# Noise-box-v001.net
KiCad netlist of a schematic drawn in EAGLE
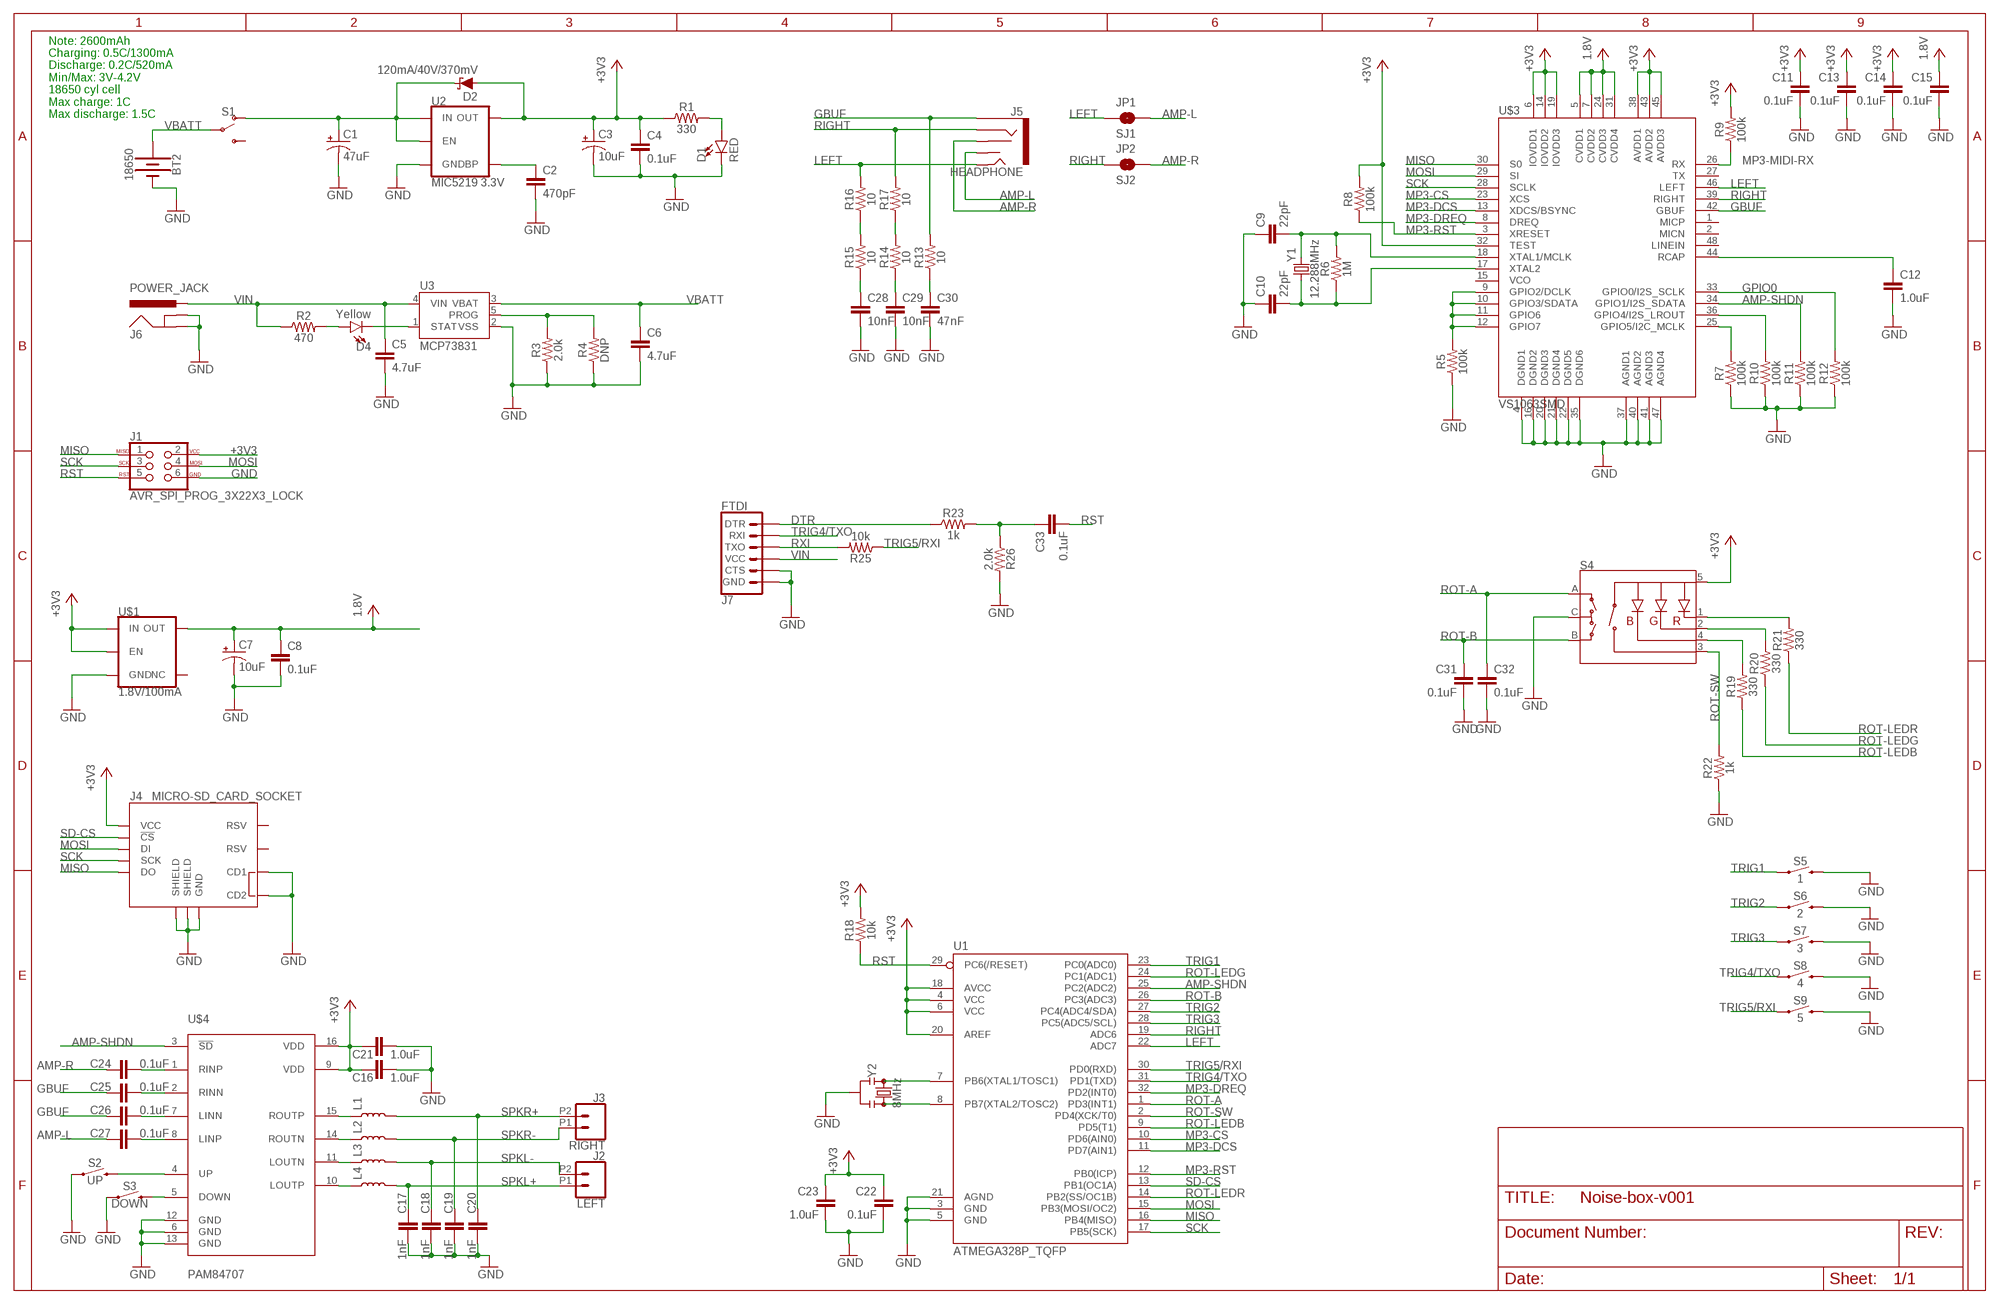
[diagram p0: schematic, sheet 1]

(export (version "E")
  (design (tool "Eeschema 10.0.6"))
  (components
    (comp (ref "BT2")
      (value "18650")
      (footprint "eagle-import:BATTERY_18650-1043P")
      (fields (field (name "MANUFACTURER") "keystone electronics") (field (name "PARTNO") "1043p"))
      (libsource (lib "eagle-import") (part "BATTERY-1043P"))
    )
    (comp (ref "C1")
      (value "47uF")
      (footprint "eagle-import:EIA3528")
      (libsource (lib "eagle-import") (part "47UF-POLAR-EIA3528-10V-10%"))
    )
    (comp (ref "C2")
      (value "470pF")
      (footprint "eagle-import:0603")
      (libsource (lib "eagle-import") (part "470PF-0603-50V-5%"))
    )
    (comp (ref "C3")
      (value "10uF")
      (footprint "eagle-import:EIA3216")
      (libsource (lib "eagle-import") (part "10UF-POLAR-EIA3216-16V-10%(TANT)"))
    )
    (comp (ref "C4")
      (value "0.1uF")
      (footprint "eagle-import:0603")
      (libsource (lib "eagle-import") (part "0.1UF-0603-25V-5%"))
    )
    (comp (ref "C5")
      (value "4.7uF")
      (footprint "eagle-import:0603")
      (libsource (lib "eagle-import") (part "4.7UF0603"))
    )
    (comp (ref "C6")
      (value "4.7uF")
      (footprint "eagle-import:0603")
      (libsource (lib "eagle-import") (part "4.7UF0603"))
    )
    (comp (ref "C7")
      (value "10uF")
      (footprint "eagle-import:EIA3216")
      (libsource (lib "eagle-import") (part "10UF-POLAR-EIA3216-16V-10%(TANT)"))
    )
    (comp (ref "C8")
      (value "0.1uF")
      (footprint "eagle-import:0603")
      (libsource (lib "eagle-import") (part "0.1UF-0603-25V-5%"))
    )
    (comp (ref "C9")
      (value "22pF")
      (footprint "eagle-import:0603")
      (libsource (lib "eagle-import") (part "22PF-0603-50V-5%"))
    )
    (comp (ref "C10")
      (value "22pF")
      (footprint "eagle-import:0603")
      (libsource (lib "eagle-import") (part "22PF-0603-50V-5%"))
    )
    (comp (ref "C11")
      (value "0.1uF")
      (footprint "eagle-import:0603")
      (libsource (lib "eagle-import") (part "0.1UF-0603-25V-5%"))
    )
    (comp (ref "C12")
      (value "1.0uF")
      (footprint "eagle-import:0603")
      (libsource (lib "eagle-import") (part "1.0UF-0603-16V-10%"))
    )
    (comp (ref "C13")
      (value "0.1uF")
      (footprint "eagle-import:0603")
      (libsource (lib "eagle-import") (part "0.1UF-0603-25V-5%"))
    )
    (comp (ref "C14")
      (value "0.1uF")
      (footprint "eagle-import:0603")
      (libsource (lib "eagle-import") (part "0.1UF-0603-25V-5%"))
    )
    (comp (ref "C15")
      (value "0.1uF")
      (footprint "eagle-import:0603")
      (libsource (lib "eagle-import") (part "0.1UF-0603-25V-5%"))
    )
    (comp (ref "C16")
      (value "1.0uF")
      (footprint "eagle-import:0603")
      (libsource (lib "eagle-import") (part "1.0UF-0603-16V-10%"))
    )
    (comp (ref "C17")
      (value "1nF")
      (footprint "eagle-import:0603")
      (libsource (lib "eagle-import") (part "1.0NF/1000PF-0603-50V-10%"))
    )
    (comp (ref "C18")
      (value "1nF")
      (footprint "eagle-import:0603")
      (libsource (lib "eagle-import") (part "1.0NF/1000PF-0603-50V-10%"))
    )
    (comp (ref "C19")
      (value "1nF")
      (footprint "eagle-import:0603")
      (libsource (lib "eagle-import") (part "1.0NF/1000PF-0603-50V-10%"))
    )
    (comp (ref "C20")
      (value "1nF")
      (footprint "eagle-import:0603")
      (libsource (lib "eagle-import") (part "1.0NF/1000PF-0603-50V-10%"))
    )
    (comp (ref "C21")
      (value "1.0uF")
      (footprint "eagle-import:0603")
      (libsource (lib "eagle-import") (part "1.0UF-0603-16V-10%"))
    )
    (comp (ref "C22")
      (value "0.1uF")
      (footprint "eagle-import:0603")
      (libsource (lib "eagle-import") (part "0.1UF-0603-25V-5%"))
    )
    (comp (ref "C23")
      (value "1.0uF")
      (footprint "eagle-import:0603")
      (libsource (lib "eagle-import") (part "1.0UF-0603-16V-10%"))
    )
    (comp (ref "C24")
      (value "0.1uF")
      (footprint "eagle-import:0603")
      (libsource (lib "eagle-import") (part "0.1UF-0603-25V-5%"))
    )
    (comp (ref "C25")
      (value "0.1uF")
      (footprint "eagle-import:0603")
      (libsource (lib "eagle-import") (part "0.1UF-0603-25V-5%"))
    )
    (comp (ref "C26")
      (value "0.1uF")
      (footprint "eagle-import:0603")
      (libsource (lib "eagle-import") (part "0.1UF-0603-25V-5%"))
    )
    (comp (ref "C27")
      (value "0.1uF")
      (footprint "eagle-import:0603")
      (libsource (lib "eagle-import") (part "0.1UF-0603-25V-5%"))
    )
    (comp (ref "C28")
      (value "10nF")
      (footprint "eagle-import:0603")
      (libsource (lib "eagle-import") (part "10NF-0603-50V-10%"))
    )
    (comp (ref "C29")
      (value "10nF")
      (footprint "eagle-import:0603")
      (libsource (lib "eagle-import") (part "10NF-0603-50V-10%"))
    )
    (comp (ref "C30")
      (value "47nF")
      (footprint "eagle-import:0603")
      (libsource (lib "eagle-import") (part "47NF-0603-25V-5%"))
    )
    (comp (ref "C31")
      (value "0.1uF")
      (footprint "eagle-import:0603")
      (libsource (lib "eagle-import") (part "0.1UF-0603-25V-5%"))
    )
    (comp (ref "C32")
      (value "0.1uF")
      (footprint "eagle-import:0603")
      (libsource (lib "eagle-import") (part "0.1UF-0603-25V-5%"))
    )
    (comp (ref "C33")
      (value "0.1uF")
      (footprint "eagle-import:0603")
      (libsource (lib "eagle-import") (part "0.1UF-0603-25V-5%"))
    )
    (comp (ref "D1")
      (value "RED")
      (footprint "eagle-import:LED-0603")
      (libsource (lib "eagle-import") (part "LED-RED0603"))
    )
    (comp (ref "D2")
      (value "120mA/40V/370mV")
      (footprint "eagle-import:SOD-523")
      (libsource (lib "eagle-import") (part "DIODE-SCHOTTKY-RB751S40"))
    )
    (comp (ref "D4")
      (value "Yellow")
      (footprint "eagle-import:LED-0603")
      (libsource (lib "eagle-import") (part "LED-YELLOW0603"))
    )
    (comp (ref "J1")
      (value "AVR_SPI_PROG_3X22X3_LOCK")
      (footprint "eagle-import:2X3_LOCK")
      (libsource (lib "eagle-import") (part "AVR_SPI_PROG_3X22X3_LOCK"))
    )
    (comp (ref "J2")
      (value "LEFT")
      (footprint "eagle-import:1X02_2.54_SCREWTERM")
      (libsource (lib "eagle-import") (part "CONN_022.54MM_SCREWTERM"))
    )
    (comp (ref "J3")
      (value "RIGHT")
      (footprint "eagle-import:1X02_2.54_SCREWTERM")
      (libsource (lib "eagle-import") (part "CONN_022.54MM_SCREWTERM"))
    )
    (comp (ref "J4")
      (value "MICRO-SD_CARD_SOCKET")
      (footprint "eagle-import:MICRO-SD-SOCKET")
      (libsource (lib "eagle-import") (part "MICRO-SD_CARD_SOCKET"))
    )
    (comp (ref "J5")
      (value "HEADPHONE")
      (footprint "eagle-import:AUDIO-JACK-3.5MM-SMD")
      (libsource (lib "eagle-import") (part "AUDIO_JACK_3.5MM_SMD"))
    )
    (comp (ref "J6")
      (value "POWER_JACK")
      (footprint "eagle-import:POWER_JACK_PTH")
      (libsource (lib "eagle-import") (part "POWER_JACK"))
    )
    (comp (ref "J7")
      (value "FTDI")
      (footprint "eagle-import:6_PIN_SERIAL_TARGET_SIDE_W_SILK")
      (libsource (lib "eagle-import") (part "6_PIN_SERIAL_TARGETSILK"))
    )
    (comp (ref "JP1")
      (value "SJ1")
      (footprint "eagle-import:SMT-JUMPER_2_NO_SILK")
      (libsource (lib "eagle-import") (part "JUMPER-SMT_2_NO_SILK"))
    )
    (comp (ref "JP2")
      (value "SJ2")
      (footprint "eagle-import:SMT-JUMPER_2_NO_SILK")
      (libsource (lib "eagle-import") (part "JUMPER-SMT_2_NO_SILK"))
    )
    (comp (ref "L1")
      (value "INDUCTOR-0805-3.3UH")
      (footprint "eagle-import:0805")
      (libsource (lib "eagle-import") (part "INDUCTOR-0805-3.3UH"))
    )
    (comp (ref "L2")
      (value "INDUCTOR-0805-3.3UH")
      (footprint "eagle-import:0805")
      (libsource (lib "eagle-import") (part "INDUCTOR-0805-3.3UH"))
    )
    (comp (ref "L3")
      (value "INDUCTOR-0805-3.3UH")
      (footprint "eagle-import:0805")
      (libsource (lib "eagle-import") (part "INDUCTOR-0805-3.3UH"))
    )
    (comp (ref "L4")
      (value "INDUCTOR-0805-3.3UH")
      (footprint "eagle-import:0805")
      (libsource (lib "eagle-import") (part "INDUCTOR-0805-3.3UH"))
    )
    (comp (ref "R1")
      (value "330")
      (footprint "eagle-import:0603")
      (libsource (lib "eagle-import") (part "330OHM-0603-1/10W-1%"))
    )
    (comp (ref "R2")
      (value "470")
      (footprint "eagle-import:0603")
      (libsource (lib "eagle-import") (part "470OHM-0603-1/10W-1%"))
    )
    (comp (ref "R3")
      (value "2.0k")
      (footprint "eagle-import:0603")
      (libsource (lib "eagle-import") (part "2.0KOHM-0603-1/10W-5%"))
    )
    (comp (ref "R4")
      (value "DNP")
      (footprint "eagle-import:0603")
      (libsource (lib "eagle-import") (part "2.0KOHM-0603-1/10W-5%"))
    )
    (comp (ref "R5")
      (value "100k")
      (footprint "eagle-import:0603")
      (libsource (lib "eagle-import") (part "100KOHM-0603-1/10W-1%"))
    )
    (comp (ref "R6")
      (value "1M")
      (footprint "eagle-import:0603")
      (libsource (lib "eagle-import") (part "1MOHM-0603-1/4W-5%"))
    )
    (comp (ref "R7")
      (value "100k")
      (footprint "eagle-import:0603")
      (libsource (lib "eagle-import") (part "100KOHM-0603-1/10W-1%"))
    )
    (comp (ref "R8")
      (value "100k")
      (footprint "eagle-import:0603")
      (libsource (lib "eagle-import") (part "100KOHM-0603-1/10W-1%"))
    )
    (comp (ref "R9")
      (value "100k")
      (footprint "eagle-import:0603")
      (libsource (lib "eagle-import") (part "100KOHM-0603-1/10W-1%"))
    )
    (comp (ref "R10")
      (value "100k")
      (footprint "eagle-import:0603")
      (libsource (lib "eagle-import") (part "100KOHM-0603-1/10W-1%"))
    )
    (comp (ref "R11")
      (value "100k")
      (footprint "eagle-import:0603")
      (libsource (lib "eagle-import") (part "100KOHM-0603-1/10W-1%"))
    )
    (comp (ref "R12")
      (value "100k")
      (footprint "eagle-import:0603")
      (libsource (lib "eagle-import") (part "100KOHM-0603-1/10W-1%"))
    )
    (comp (ref "R13")
      (value "10")
      (footprint "eagle-import:0603")
      (libsource (lib "eagle-import") (part "10OHM-0603-1/10W-5%"))
    )
    (comp (ref "R14")
      (value "10")
      (footprint "eagle-import:0603")
      (libsource (lib "eagle-import") (part "10OHM-0603-1/10W-5%"))
    )
    (comp (ref "R15")
      (value "10")
      (footprint "eagle-import:0603")
      (libsource (lib "eagle-import") (part "10OHM-0603-1/10W-5%"))
    )
    (comp (ref "R16")
      (value "10")
      (footprint "eagle-import:0603")
      (libsource (lib "eagle-import") (part "10OHM-0603-1/10W-5%"))
    )
    (comp (ref "R17")
      (value "10")
      (footprint "eagle-import:0603")
      (libsource (lib "eagle-import") (part "10OHM-0603-1/10W-5%"))
    )
    (comp (ref "R18")
      (value "10k")
      (footprint "eagle-import:0603")
      (libsource (lib "eagle-import") (part "10KOHM-0603-1/10W-1%"))
    )
    (comp (ref "R19")
      (value "330")
      (footprint "eagle-import:0603")
      (libsource (lib "eagle-import") (part "330OHM-0603-1/10W-1%"))
    )
    (comp (ref "R20")
      (value "330")
      (footprint "eagle-import:0603")
      (libsource (lib "eagle-import") (part "330OHM-0603-1/10W-1%"))
    )
    (comp (ref "R21")
      (value "330")
      (footprint "eagle-import:0603")
      (libsource (lib "eagle-import") (part "330OHM-0603-1/10W-1%"))
    )
    (comp (ref "R22")
      (value "1k")
      (footprint "eagle-import:0603")
      (libsource (lib "eagle-import") (part "1KOHM-0603-1/10W-1%"))
    )
    (comp (ref "R23")
      (value "1k")
      (footprint "eagle-import:0603")
      (libsource (lib "eagle-import") (part "1KOHM-0603-1/10W-1%"))
    )
    (comp (ref "R25")
      (value "10k")
      (footprint "eagle-import:0603")
      (libsource (lib "eagle-import") (part "10KOHM-0603-1/10W-1%"))
    )
    (comp (ref "R26")
      (value "2.0k")
      (footprint "eagle-import:0603")
      (libsource (lib "eagle-import") (part "2.0KOHM-0603-1/10W-5%"))
    )
    (comp (ref "S1")
      (value "SWITCH-SPDT-SMD-RIGHT-ANGLE")
      (footprint "eagle-import:SWITCH_SPST_SMD_A")
      (libsource (lib "eagle-import") (part "SWITCH-SPDT-SMD-RIGHT-ANGLE"))
    )
    (comp (ref "S2")
      (value "UP")
      (footprint "eagle-import:TACTILE_SWITCH_SMD_4.5MM")
      (libsource (lib "eagle-import") (part "MOMENTARY-SWITCH-SPST-SMD-4.5MM"))
    )
    (comp (ref "S3")
      (value "DOWN")
      (footprint "eagle-import:TACTILE_SWITCH_SMD_4.5MM")
      (libsource (lib "eagle-import") (part "MOMENTARY-SWITCH-SPST-SMD-4.5MM"))
    )
    (comp (ref "S4")
      (value "ENCODER-RGB-SWITCH")
      (footprint "eagle-import:ENCODER_LED_3")
      (libsource (lib "eagle-import") (part "ENCODER-RGB-SWITCH"))
    )
    (comp (ref "S5")
      (value "1")
      (footprint "eagle-import:TACTILE_SWITCH_SMD_4.5MM")
      (libsource (lib "eagle-import") (part "MOMENTARY-SWITCH-SPST-SMD-4.5MM"))
    )
    (comp (ref "S6")
      (value "2")
      (footprint "eagle-import:TACTILE_SWITCH_SMD_4.5MM")
      (libsource (lib "eagle-import") (part "MOMENTARY-SWITCH-SPST-SMD-4.5MM"))
    )
    (comp (ref "S7")
      (value "3")
      (footprint "eagle-import:TACTILE_SWITCH_SMD_4.5MM")
      (libsource (lib "eagle-import") (part "MOMENTARY-SWITCH-SPST-SMD-4.5MM"))
    )
    (comp (ref "S8")
      (value "4")
      (footprint "eagle-import:TACTILE_SWITCH_SMD_4.5MM")
      (libsource (lib "eagle-import") (part "MOMENTARY-SWITCH-SPST-SMD-4.5MM"))
    )
    (comp (ref "S9")
      (value "5")
      (footprint "eagle-import:TACTILE_SWITCH_SMD_4.5MM")
      (libsource (lib "eagle-import") (part "MOMENTARY-SWITCH-SPST-SMD-4.5MM"))
    )
    (comp (ref "U$1")
      (value "1.8V/100mA")
      (footprint "eagle-import:SC70")
      (libsource (lib "eagle-import") (part "V_REG_SP6214-1.8V"))
    )
    (comp (ref "U$3")
      (value "VS1063SMD")
      (footprint "eagle-import:LQFP-48")
      (libsource (lib "eagle-import") (part "VS1063SMD"))
    )
    (comp (ref "U$4")
      (value "PAM84707")
      (footprint "eagle-import:SO16")
      (fields (field (name "PARTNO") "PAM8407DRDICT-ND"))
      (libsource (lib "eagle-import") (part "PAM8407"))
    )
    (comp (ref "U1")
      (value "ATMEGA328P_TQFP")
      (footprint "eagle-import:TQFP32-08")
      (libsource (lib "eagle-import") (part "ATMEGA328P_TQFP"))
    )
    (comp (ref "U2")
      (value "MIC5219 3.3V")
      (footprint "eagle-import:SOT23-5")
      (libsource (lib "eagle-import") (part "V_REG_MIC52193.3V"))
    )
    (comp (ref "U3")
      (value "MCP73831")
      (footprint "eagle-import:SOT23-5")
      (libsource (lib "eagle-import") (part "MCP73831"))
    )
    (comp (ref "Y1")
      (value "12.288MHz")
      (footprint "eagle-import:CRYSTAL-SMD-5X3.2-4PAD")
      (libsource (lib "eagle-import") (part "CRYSTAL-12.288MHZ{dblquote}"))
    )
    (comp (ref "Y2")
      (value "8MHz")
      (footprint "eagle-import:RESONATOR-SMD-3.2X1.3")
      (libsource (lib "eagle-import") (part "RESONATOR-8MHZSMD_3.2X1.3"))
    )
  )
  (nets
    (net (code "1") (name "+3V3") (class "Default")
      (node (ref "C11") (pin "1") (pinfunction "1_1") (pintype "passive"))
      (node (ref "C13") (pin "1") (pinfunction "1_1") (pintype "passive"))
      (node (ref "C14") (pin "1") (pinfunction "1_1") (pintype "passive"))
      (node (ref "C16") (pin "1") (pinfunction "1_1") (pintype "passive"))
      (node (ref "C21") (pin "1") (pinfunction "1_1") (pintype "passive"))
      (node (ref "C22") (pin "1") (pinfunction "1_1") (pintype "passive"))
      (node (ref "C23") (pin "1") (pinfunction "1_1") (pintype "passive"))
      (node (ref "C3") (pin "+") (pinfunction "+_+") (pintype "passive"))
      (node (ref "C4") (pin "1") (pinfunction "1_1") (pintype "passive"))
      (node (ref "D2") (pin "A") (pinfunction "A_A") (pintype "passive"))
      (node (ref "J1") (pin "2") (pinfunction "2_2") (pintype "passive"))
      (node (ref "J4") (pin "VCC") (pinfunction "VCC_VCC") (pintype "bidirectional"))
      (node (ref "R1") (pin "1") (pinfunction "1_1") (pintype "passive"))
      (node (ref "R18") (pin "2") (pinfunction "2_2") (pintype "passive"))
      (node (ref "R8") (pin "2") (pinfunction "2_2") (pintype "passive"))
      (node (ref "R9") (pin "2") (pinfunction "2_2") (pintype "passive"))
      (node (ref "S4") (pin "5") (pinfunction "+_5") (pintype "passive"))
      (node (ref "U$1") (pin "1") (pinfunction "IN_1") (pintype "input"))
      (node (ref "U$1") (pin "3") (pinfunction "EN_3") (pintype "input"))
      (node (ref "U$3") (pin "14") (pinfunction "IOVDD2_14") (pintype "bidirectional"))
      (node (ref "U$3") (pin "19") (pinfunction "IOVDD3_19") (pintype "bidirectional"))
      (node (ref "U$3") (pin "32") (pinfunction "TEST_32") (pintype "bidirectional"))
      (node (ref "U$3") (pin "38") (pinfunction "AVDD1_38") (pintype "bidirectional"))
      (node (ref "U$3") (pin "43") (pinfunction "AVDD2_43") (pintype "bidirectional"))
      (node (ref "U$3") (pin "45") (pinfunction "AVDD3_45") (pintype "bidirectional"))
      (node (ref "U$3") (pin "6") (pinfunction "IOVDD1_6") (pintype "bidirectional"))
      (node (ref "U$4") (pin "16") (pinfunction "VDD_16") (pintype "bidirectional"))
      (node (ref "U$4") (pin "9") (pinfunction "VDD_9") (pintype "bidirectional"))
      (node (ref "U1") (pin "18") (pinfunction "AVCC_18") (pintype "bidirectional"))
      (node (ref "U1") (pin "20") (pinfunction "AREF_20") (pintype "bidirectional"))
      (node (ref "U1") (pin "4") (pinfunction "VCC_4") (pintype "bidirectional"))
      (node (ref "U1") (pin "6") (pinfunction "VCC_6") (pintype "bidirectional"))
      (node (ref "U2") (pin "5") (pinfunction "OUT_5") (pintype "passive"))
    )
    (net (code "2") (name "/AMP-L") (class "Default")
      (node (ref "C27") (pin "1") (pinfunction "1_1") (pintype "passive"))
      (node (ref "J5") (pin "TSH") (pinfunction "TSH_TSH") (pintype "bidirectional"))
      (node (ref "JP1") (pin "2") (pinfunction "2_2") (pintype "passive"))
    )
    (net (code "3") (name "/AMP-R") (class "Default")
      (node (ref "C24") (pin "1") (pinfunction "1_1") (pintype "passive"))
      (node (ref "J5") (pin "RSH") (pinfunction "RSH_RSH") (pintype "bidirectional"))
      (node (ref "JP2") (pin "2") (pinfunction "2_2") (pintype "passive"))
    )
    (net (code "4") (name "/AMP-SHDN") (class "Default")
      (node (ref "R11") (pin "2") (pinfunction "2_2") (pintype "passive"))
      (node (ref "U$3") (pin "34") (pinfunction "GPIO1/I2S_SDATA_34") (pintype "bidirectional"))
      (node (ref "U$4") (pin "3") (pinfunction "~{SD}_3") (pintype "bidirectional"))
      (node (ref "U1") (pin "25") (pinfunction "PC2(ADC2)_25") (pintype "bidirectional"))
    )
    (net (code "5") (name "/DTR") (class "Default")
      (node (ref "J7") (pin "P$1") (pinfunction "DTR_P$1") (pintype "passive"))
      (node (ref "R23") (pin "1") (pinfunction "1_1") (pintype "passive"))
    )
    (net (code "6") (name "/GBUF") (class "Default")
      (node (ref "C25") (pin "1") (pinfunction "1_1") (pintype "passive"))
      (node (ref "C26") (pin "1") (pinfunction "1_1") (pintype "passive"))
      (node (ref "J5") (pin "SLEEVE") (pinfunction "SLEEVE_SLEEVE") (pintype "bidirectional"))
      (node (ref "R13") (pin "2") (pinfunction "2_2") (pintype "passive"))
      (node (ref "U$3") (pin "42") (pinfunction "GBUF_42") (pintype "bidirectional"))
    )
    (net (code "7") (name "/GPIO0") (class "Default")
      (node (ref "R12") (pin "2") (pinfunction "2_2") (pintype "passive"))
      (node (ref "U$3") (pin "33") (pinfunction "GPIO0/I2S_SCLK_33") (pintype "bidirectional"))
    )
    (net (code "8") (name "/LEFT") (class "Default")
      (node (ref "J5") (pin "TIP") (pinfunction "TIP_TIP") (pintype "bidirectional"))
      (node (ref "JP1") (pin "1") (pinfunction "1_1") (pintype "passive"))
      (node (ref "R16") (pin "2") (pinfunction "2_2") (pintype "passive"))
      (node (ref "U$3") (pin "46") (pinfunction "LEFT_46") (pintype "bidirectional"))
      (node (ref "U1") (pin "22") (pinfunction "ADC7_22") (pintype "bidirectional"))
    )
    (net (code "9") (name "/MISO") (class "Default")
      (node (ref "J1") (pin "1") (pinfunction "1_1") (pintype "passive"))
      (node (ref "J4") (pin "DO") (pinfunction "DO_DO") (pintype "bidirectional"))
      (node (ref "U$3") (pin "30") (pinfunction "S0_30") (pintype "bidirectional"))
      (node (ref "U1") (pin "16") (pinfunction "PB4(MISO)_16") (pintype "bidirectional"))
    )
    (net (code "10") (name "/MOSI") (class "Default")
      (node (ref "J1") (pin "4") (pinfunction "4_4") (pintype "passive"))
      (node (ref "J4") (pin "DI") (pinfunction "DI_DI") (pintype "bidirectional"))
      (node (ref "U$3") (pin "29") (pinfunction "SI_29") (pintype "bidirectional"))
      (node (ref "U1") (pin "15") (pinfunction "PB3(MOSI/OC2)_15") (pintype "bidirectional"))
    )
    (net (code "11") (name "/MP3-CS") (class "Default")
      (node (ref "U$3") (pin "23") (pinfunction "XCS_23") (pintype "bidirectional"))
      (node (ref "U1") (pin "10") (pinfunction "PD6(AIN0)_10") (pintype "bidirectional"))
    )
    (net (code "12") (name "/MP3-DCS") (class "Default")
      (node (ref "U$3") (pin "13") (pinfunction "XDCS/BSYNC_13") (pintype "bidirectional"))
      (node (ref "U1") (pin "11") (pinfunction "PD7(AIN1)_11") (pintype "bidirectional"))
    )
    (net (code "13") (name "/MP3-DREQ") (class "Default")
      (node (ref "U$3") (pin "8") (pinfunction "DREQ_8") (pintype "bidirectional"))
      (node (ref "U1") (pin "32") (pinfunction "PD2(INT0)_32") (pintype "bidirectional"))
    )
    (net (code "14") (name "/MP3-MIDI-RX") (class "Default")
      (node (ref "R9") (pin "1") (pinfunction "1_1") (pintype "passive"))
      (node (ref "U$3") (pin "26") (pinfunction "RX_26") (pintype "bidirectional"))
    )
    (net (code "15") (name "/MP3-RST") (class "Default")
      (node (ref "R8") (pin "1") (pinfunction "1_1") (pintype "passive"))
      (node (ref "U$3") (pin "3") (pinfunction "XRESET_3") (pintype "bidirectional"))
      (node (ref "U1") (pin "12") (pinfunction "PB0(ICP)_12") (pintype "bidirectional"))
    )
    (net (code "16") (name "/RIGHT") (class "Default")
      (node (ref "J5") (pin "RING") (pinfunction "RING_RING") (pintype "bidirectional"))
      (node (ref "JP2") (pin "1") (pinfunction "1_1") (pintype "passive"))
      (node (ref "R17") (pin "2") (pinfunction "2_2") (pintype "passive"))
      (node (ref "U$3") (pin "39") (pinfunction "RIGHT_39") (pintype "bidirectional"))
      (node (ref "U1") (pin "19") (pinfunction "ADC6_19") (pintype "bidirectional"))
    )
    (net (code "17") (name "/ROT-A") (class "Default")
      (node (ref "C32") (pin "1") (pinfunction "1_1") (pintype "passive"))
      (node (ref "S4") (pin "A") (pinfunction "A_A") (pintype "bidirectional"))
      (node (ref "U1") (pin "1") (pinfunction "PD3(INT1)_1") (pintype "bidirectional"))
    )
    (net (code "18") (name "/ROT-B") (class "Default")
      (node (ref "C31") (pin "1") (pinfunction "1_1") (pintype "passive"))
      (node (ref "S4") (pin "B") (pinfunction "B_B") (pintype "bidirectional"))
      (node (ref "U1") (pin "26") (pinfunction "PC3(ADC3)_26") (pintype "bidirectional"))
    )
    (net (code "19") (name "/ROT-LEDB") (class "Default")
      (node (ref "R19") (pin "1") (pinfunction "1_1") (pintype "passive"))
      (node (ref "U1") (pin "9") (pinfunction "PD5(T1)_9") (pintype "bidirectional"))
    )
    (net (code "20") (name "/ROT-LEDG") (class "Default")
      (node (ref "R20") (pin "1") (pinfunction "1_1") (pintype "passive"))
      (node (ref "U1") (pin "24") (pinfunction "PC1(ADC1)_24") (pintype "bidirectional"))
    )
    (net (code "21") (name "/ROT-LEDR") (class "Default")
      (node (ref "R21") (pin "1") (pinfunction "1_1") (pintype "passive"))
      (node (ref "U1") (pin "14") (pinfunction "PB2(SS/OC1B)_14") (pintype "bidirectional"))
    )
    (net (code "22") (name "/ROT-SW") (class "Default")
      (node (ref "R22") (pin "2") (pinfunction "2_2") (pintype "passive"))
      (node (ref "S4") (pin "3") (pinfunction "SW_3") (pintype "passive"))
      (node (ref "U1") (pin "2") (pinfunction "PD4(XCK/T0)_2") (pintype "bidirectional"))
    )
    (net (code "23") (name "/RST") (class "Default")
      (node (ref "C33") (pin "2") (pinfunction "2_2") (pintype "passive"))
      (node (ref "J1") (pin "5") (pinfunction "5_5") (pintype "passive"))
      (node (ref "R18") (pin "1") (pinfunction "1_1") (pintype "passive"))
      (node (ref "U1") (pin "29") (pinfunction "PC6(/RESET)_29") (pintype "bidirectional"))
    )
    (net (code "24") (name "/RXI") (class "Default")
      (node (ref "J7") (pin "P$2") (pinfunction "TXO_P$2") (pintype "passive"))
      (node (ref "R25") (pin "2") (pinfunction "2_2") (pintype "passive"))
    )
    (net (code "25") (name "/SCK") (class "Default")
      (node (ref "J1") (pin "3") (pinfunction "3_3") (pintype "passive"))
      (node (ref "J4") (pin "SCLK") (pinfunction "SCK_SCLK") (pintype "bidirectional"))
      (node (ref "U$3") (pin "28") (pinfunction "SCLK_28") (pintype "bidirectional"))
      (node (ref "U1") (pin "17") (pinfunction "PB5(SCK)_17") (pintype "bidirectional"))
    )
    (net (code "26") (name "/SD-CS") (class "Default")
      (node (ref "J4") (pin "CS") (pinfunction "~{CS}_CS") (pintype "bidirectional"))
      (node (ref "U1") (pin "13") (pinfunction "PB1(OC1A)_13") (pintype "bidirectional"))
    )
    (net (code "27") (name "/SPKL+") (class "Default")
      (node (ref "C17") (pin "1") (pinfunction "1_1") (pintype "passive"))
      (node (ref "J2") (pin "P1") (pinfunction "1_P1") (pintype "passive"))
      (node (ref "L4") (pin "2") (pinfunction "2_2") (pintype "passive"))
    )
    (net (code "28") (name "/SPKL-") (class "Default")
      (node (ref "C18") (pin "1") (pinfunction "1_1") (pintype "passive"))
      (node (ref "J2") (pin "P2") (pinfunction "2_P2") (pintype "passive"))
      (node (ref "L3") (pin "2") (pinfunction "2_2") (pintype "passive"))
    )
    (net (code "29") (name "/SPKR+") (class "Default")
      (node (ref "C20") (pin "1") (pinfunction "1_1") (pintype "passive"))
      (node (ref "J3") (pin "P2") (pinfunction "2_P2") (pintype "passive"))
      (node (ref "L1") (pin "2") (pinfunction "2_2") (pintype "passive"))
    )
    (net (code "30") (name "/SPKR-") (class "Default")
      (node (ref "C19") (pin "1") (pinfunction "1_1") (pintype "passive"))
      (node (ref "J3") (pin "P1") (pinfunction "1_P1") (pintype "passive"))
      (node (ref "L2") (pin "2") (pinfunction "2_2") (pintype "passive"))
    )
    (net (code "31") (name "/TRIG1") (class "Default")
      (node (ref "S5") (pin "2") (pinfunction "1_2") (pintype "passive"))
      (node (ref "S5") (pin "3") (pinfunction "1_3") (pintype "passive"))
      (node (ref "U1") (pin "23") (pinfunction "PC0(ADC0)_23") (pintype "bidirectional"))
    )
    (net (code "32") (name "/TRIG2") (class "Default")
      (node (ref "S6") (pin "2") (pinfunction "1_2") (pintype "passive"))
      (node (ref "S6") (pin "3") (pinfunction "1_3") (pintype "passive"))
      (node (ref "U1") (pin "27") (pinfunction "PC4(ADC4/SDA)_27") (pintype "bidirectional"))
    )
    (net (code "33") (name "/TRIG3") (class "Default")
      (node (ref "S7") (pin "2") (pinfunction "1_2") (pintype "passive"))
      (node (ref "S7") (pin "3") (pinfunction "1_3") (pintype "passive"))
      (node (ref "U1") (pin "28") (pinfunction "PC5(ADC5/SCL)_28") (pintype "bidirectional"))
    )
    (net (code "34") (name "/TRIG4{slash}TXO") (class "Default")
      (node (ref "J7") (pin "P$3") (pinfunction "RXI_P$3") (pintype "passive"))
      (node (ref "S8") (pin "2") (pinfunction "1_2") (pintype "passive"))
      (node (ref "S8") (pin "3") (pinfunction "1_3") (pintype "passive"))
      (node (ref "U1") (pin "31") (pinfunction "PD1(TXD)_31") (pintype "bidirectional"))
    )
    (net (code "35") (name "/TRIG5{slash}RXI") (class "Default")
      (node (ref "R25") (pin "1") (pinfunction "1_1") (pintype "passive"))
      (node (ref "S9") (pin "2") (pinfunction "1_2") (pintype "passive"))
      (node (ref "S9") (pin "3") (pinfunction "1_3") (pintype "passive"))
      (node (ref "U1") (pin "30") (pinfunction "PD0(RXD)_30") (pintype "bidirectional"))
    )
    (net (code "36") (name "/VBATT") (class "Default")
      (node (ref "BT2") (pin "PWR@1") (pinfunction "+_PWR@1") (pintype "power_in"))
      (node (ref "C6") (pin "1") (pinfunction "1_1") (pintype "passive"))
      (node (ref "S1") (pin "2") (pinfunction "P_2") (pintype "passive"))
      (node (ref "U3") (pin "3") (pinfunction "VBAT_3") (pintype "power_in"))
    )
    (net (code "37") (name "/VIN") (class "Default")
      (node (ref "C5") (pin "1") (pinfunction "1_1") (pintype "passive"))
      (node (ref "J6") (pin "PWR") (pinfunction "PWR_PWR") (pintype "bidirectional"))
      (node (ref "J7") (pin "P$4") (pinfunction "VCC_P$4") (pintype "passive"))
      (node (ref "R2") (pin "1") (pinfunction "1_1") (pintype "passive"))
      (node (ref "U3") (pin "4") (pinfunction "VIN_4") (pintype "power_in"))
    )
    (net (code "38") (name "1.8V") (class "Default")
      (node (ref "C15") (pin "1") (pinfunction "1_1") (pintype "passive"))
      (node (ref "C7") (pin "+") (pinfunction "+_+") (pintype "passive"))
      (node (ref "C8") (pin "1") (pinfunction "1_1") (pintype "passive"))
      (node (ref "U$1") (pin "5") (pinfunction "OUT_5") (pintype "passive"))
      (node (ref "U$3") (pin "24") (pinfunction "CVDD3_24") (pintype "bidirectional"))
      (node (ref "U$3") (pin "31") (pinfunction "CVDD4_31") (pintype "bidirectional"))
      (node (ref "U$3") (pin "5") (pinfunction "CVDD1_5") (pintype "bidirectional"))
      (node (ref "U$3") (pin "7") (pinfunction "CVDD2_7") (pintype "bidirectional"))
    )
    (net (code "39") (name "GND") (class "Default")
      (node (ref "BT2") (pin "GND@1") (pinfunction "-_GND@1") (pintype "power_in"))
      (node (ref "C1") (pin "C") (pinfunction "-_C") (pintype "passive"))
      (node (ref "C10") (pin "1") (pinfunction "1_1") (pintype "passive"))
      (node (ref "C11") (pin "2") (pinfunction "2_2") (pintype "passive"))
      (node (ref "C12") (pin "2") (pinfunction "2_2") (pintype "passive"))
      (node (ref "C13") (pin "2") (pinfunction "2_2") (pintype "passive"))
      (node (ref "C14") (pin "2") (pinfunction "2_2") (pintype "passive"))
      (node (ref "C15") (pin "2") (pinfunction "2_2") (pintype "passive"))
      (node (ref "C16") (pin "2") (pinfunction "2_2") (pintype "passive"))
      (node (ref "C17") (pin "2") (pinfunction "2_2") (pintype "passive"))
      (node (ref "C18") (pin "2") (pinfunction "2_2") (pintype "passive"))
      (node (ref "C19") (pin "2") (pinfunction "2_2") (pintype "passive"))
      (node (ref "C2") (pin "2") (pinfunction "2_2") (pintype "passive"))
      (node (ref "C20") (pin "2") (pinfunction "2_2") (pintype "passive"))
      (node (ref "C21") (pin "2") (pinfunction "2_2") (pintype "passive"))
      (node (ref "C22") (pin "2") (pinfunction "2_2") (pintype "passive"))
      (node (ref "C23") (pin "2") (pinfunction "2_2") (pintype "passive"))
      (node (ref "C28") (pin "2") (pinfunction "2_2") (pintype "passive"))
      (node (ref "C29") (pin "2") (pinfunction "2_2") (pintype "passive"))
      (node (ref "C3") (pin "-") (pinfunction "-_-") (pintype "passive"))
      (node (ref "C30") (pin "2") (pinfunction "2_2") (pintype "passive"))
      (node (ref "C31") (pin "2") (pinfunction "2_2") (pintype "passive"))
      (node (ref "C32") (pin "2") (pinfunction "2_2") (pintype "passive"))
      (node (ref "C4") (pin "2") (pinfunction "2_2") (pintype "passive"))
      (node (ref "C5") (pin "2") (pinfunction "2_2") (pintype "passive"))
      (node (ref "C6") (pin "2") (pinfunction "2_2") (pintype "passive"))
      (node (ref "C7") (pin "-") (pinfunction "-_-") (pintype "passive"))
      (node (ref "C8") (pin "2") (pinfunction "2_2") (pintype "passive"))
      (node (ref "C9") (pin "1") (pinfunction "1_1") (pintype "passive"))
      (node (ref "D1") (pin "C") (pinfunction "C_C") (pintype "passive"))
      (node (ref "J1") (pin "6") (pinfunction "6_6") (pintype "passive"))
      (node (ref "J4") (pin "CD1") (pinfunction "CD1_CD1") (pintype "bidirectional"))
      (node (ref "J4") (pin "CD2") (pinfunction "CD2_CD2") (pintype "bidirectional"))
      (node (ref "J4") (pin "GND") (pinfunction "GND_GND") (pintype "bidirectional"))
      (node (ref "J4") (pin "GND1") (pinfunction "SHIELD_GND1") (pintype "bidirectional"))
      (node (ref "J4") (pin "GND3") (pinfunction "SHIELD_GND3") (pintype "bidirectional"))
      (node (ref "J6") (pin "GND") (pinfunction "GND_GND") (pintype "bidirectional"))
      (node (ref "J6") (pin "GNDBREAK") (pinfunction "GNDBREAK_GNDBREAK") (pintype "bidirectional"))
      (node (ref "J7") (pin "P$5") (pinfunction "CTS_P$5") (pintype "passive"))
      (node (ref "J7") (pin "P$6") (pinfunction "GND_P$6") (pintype "passive"))
      (node (ref "R10") (pin "1") (pinfunction "1_1") (pintype "passive"))
      (node (ref "R11") (pin "1") (pinfunction "1_1") (pintype "passive"))
      (node (ref "R12") (pin "1") (pinfunction "1_1") (pintype "passive"))
      (node (ref "R22") (pin "1") (pinfunction "1_1") (pintype "passive"))
      (node (ref "R26") (pin "2") (pinfunction "2_2") (pintype "passive"))
      (node (ref "R3") (pin "1") (pinfunction "1_1") (pintype "passive"))
      (node (ref "R4") (pin "1") (pinfunction "1_1") (pintype "passive"))
      (node (ref "R5") (pin "1") (pinfunction "1_1") (pintype "passive"))
      (node (ref "R7") (pin "1") (pinfunction "1_1") (pintype "passive"))
      (node (ref "S2") (pin "2") (pinfunction "1_2") (pintype "passive"))
      (node (ref "S2") (pin "3") (pinfunction "1_3") (pintype "passive"))
      (node (ref "S3") (pin "2") (pinfunction "1_2") (pintype "passive"))
      (node (ref "S3") (pin "3") (pinfunction "1_3") (pintype "passive"))
      (node (ref "S4") (pin "C") (pinfunction "C_C") (pintype "bidirectional"))
      (node (ref "S5") (pin "1") (pinfunction "2_1") (pintype "passive"))
      (node (ref "S5") (pin "4") (pinfunction "2_4") (pintype "passive"))
      (node (ref "S6") (pin "1") (pinfunction "2_1") (pintype "passive"))
      (node (ref "S6") (pin "4") (pinfunction "2_4") (pintype "passive"))
      (node (ref "S7") (pin "1") (pinfunction "2_1") (pintype "passive"))
      (node (ref "S7") (pin "4") (pinfunction "2_4") (pintype "passive"))
      (node (ref "S8") (pin "1") (pinfunction "2_1") (pintype "passive"))
      (node (ref "S8") (pin "4") (pinfunction "2_4") (pintype "passive"))
      (node (ref "S9") (pin "1") (pinfunction "2_1") (pintype "passive"))
      (node (ref "S9") (pin "4") (pinfunction "2_4") (pintype "passive"))
      (node (ref "U$1") (pin "2") (pinfunction "GND_2") (pintype "input"))
      (node (ref "U$3") (pin "16") (pinfunction "DGND2_16") (pintype "bidirectional"))
      (node (ref "U$3") (pin "20") (pinfunction "DGND3_20") (pintype "bidirectional"))
      (node (ref "U$3") (pin "21") (pinfunction "DGND4_21") (pintype "bidirectional"))
      (node (ref "U$3") (pin "22") (pinfunction "DGND5_22") (pintype "bidirectional"))
      (node (ref "U$3") (pin "35") (pinfunction "DGND6_35") (pintype "bidirectional"))
      (node (ref "U$3") (pin "37") (pinfunction "AGND1_37") (pintype "bidirectional"))
      (node (ref "U$3") (pin "4") (pinfunction "DGND1_4") (pintype "bidirectional"))
      (node (ref "U$3") (pin "40") (pinfunction "AGND2_40") (pintype "bidirectional"))
      (node (ref "U$3") (pin "41") (pinfunction "AGND3_41") (pintype "bidirectional"))
      (node (ref "U$3") (pin "47") (pinfunction "AGND4_47") (pintype "bidirectional"))
      (node (ref "U$4") (pin "12") (pinfunction "GND_12") (pintype "bidirectional"))
      (node (ref "U$4") (pin "13") (pinfunction "GND_13") (pintype "bidirectional"))
      (node (ref "U$4") (pin "6") (pinfunction "GND_6") (pintype "bidirectional"))
      (node (ref "U1") (pin "21") (pinfunction "AGND_21") (pintype "bidirectional"))
      (node (ref "U1") (pin "3") (pinfunction "GND_3") (pintype "bidirectional"))
      (node (ref "U1") (pin "5") (pinfunction "GND_5") (pintype "bidirectional"))
      (node (ref "U2") (pin "2") (pinfunction "GND_2") (pintype "input"))
      (node (ref "U3") (pin "2") (pinfunction "VSS_2") (pintype "power_in"))
      (node (ref "Y2") (pin "2") (pinfunction "2_2") (pintype "passive"))
    )
    (net (code "40") (name "Net-(C1-+)") (class "Default")
      (node (ref "C1") (pin "A") (pinfunction "+_A") (pintype "passive"))
      (node (ref "D2") (pin "C") (pinfunction "C_C") (pintype "passive"))
      (node (ref "S1") (pin "1") (pinfunction "O_1") (pintype "passive"))
      (node (ref "U2") (pin "1") (pinfunction "IN_1") (pintype "input"))
      (node (ref "U2") (pin "3") (pinfunction "EN_3") (pintype "input"))
    )
    (net (code "41") (name "Net-(C28-Pad1)") (class "Default")
      (node (ref "C28") (pin "1") (pinfunction "1_1") (pintype "passive"))
      (node (ref "R15") (pin "1") (pinfunction "1_1") (pintype "passive"))
    )
    (net (code "42") (name "Net-(C29-Pad1)") (class "Default")
      (node (ref "C29") (pin "1") (pinfunction "1_1") (pintype "passive"))
      (node (ref "R14") (pin "1") (pinfunction "1_1") (pintype "passive"))
    )
    (net (code "43") (name "Net-(C30-Pad1)") (class "Default")
      (node (ref "C30") (pin "1") (pinfunction "1_1") (pintype "passive"))
      (node (ref "R13") (pin "1") (pinfunction "1_1") (pintype "passive"))
    )
    (net (code "44") (name "Net-(C33-Pad1)") (class "Default")
      (node (ref "C33") (pin "1") (pinfunction "1_1") (pintype "passive"))
      (node (ref "R23") (pin "2") (pinfunction "2_2") (pintype "passive"))
      (node (ref "R26") (pin "1") (pinfunction "1_1") (pintype "passive"))
    )
    (net (code "45") (name "Net-(D1-PadA)") (class "Default")
      (node (ref "D1") (pin "A") (pinfunction "A_A") (pintype "passive"))
      (node (ref "R1") (pin "2") (pinfunction "2_2") (pintype "passive"))
    )
    (net (code "46") (name "Net-(D4-PadA)") (class "Default")
      (node (ref "D4") (pin "A") (pinfunction "A_A") (pintype "passive"))
      (node (ref "R2") (pin "2") (pinfunction "2_2") (pintype "passive"))
    )
    (net (code "47") (name "Net-(R14-Pad2)") (class "Default")
      (node (ref "R14") (pin "2") (pinfunction "2_2") (pintype "passive"))
      (node (ref "R17") (pin "1") (pinfunction "1_1") (pintype "passive"))
    )
    (net (code "48") (name "Net-(R15-Pad2)") (class "Default")
      (node (ref "R15") (pin "2") (pinfunction "2_2") (pintype "passive"))
      (node (ref "R16") (pin "1") (pinfunction "1_1") (pintype "passive"))
    )
    (net (code "49") (name "Net-(S4--B)") (class "Default")
      (node (ref "R19") (pin "2") (pinfunction "2_2") (pintype "passive"))
      (node (ref "S4") (pin "4") (pinfunction "-B_4") (pintype "passive"))
    )
    (net (code "50") (name "Net-(S4--G)") (class "Default")
      (node (ref "R20") (pin "2") (pinfunction "2_2") (pintype "passive"))
      (node (ref "S4") (pin "2") (pinfunction "-G_2") (pintype "passive"))
    )
    (net (code "51") (name "Net-(S4--R)") (class "Default")
      (node (ref "R21") (pin "2") (pinfunction "2_2") (pintype "passive"))
      (node (ref "S4") (pin "1") (pinfunction "-R_1") (pintype "passive"))
    )
    (net (code "52") (name "Net-(U$3-GPIO2{slash}DCLK)") (class "Default")
      (node (ref "R5") (pin "2") (pinfunction "2_2") (pintype "passive"))
      (node (ref "U$3") (pin "10") (pinfunction "GPIO3/SDATA_10") (pintype "bidirectional"))
      (node (ref "U$3") (pin "11") (pinfunction "GPIO6_11") (pintype "bidirectional"))
      (node (ref "U$3") (pin "12") (pinfunction "GPIO7_12") (pintype "bidirectional"))
      (node (ref "U$3") (pin "9") (pinfunction "GPIO2/DCLK_9") (pintype "bidirectional"))
    )
    (net (code "53") (name "Net-(U$3-GPIO4{slash}I2S_LROUT)") (class "Default")
      (node (ref "R10") (pin "2") (pinfunction "2_2") (pintype "passive"))
      (node (ref "U$3") (pin "36") (pinfunction "GPIO4/I2S_LROUT_36") (pintype "bidirectional"))
    )
    (net (code "54") (name "Net-(U$3-GPIO5{slash}I2C_MCLK)") (class "Default")
      (node (ref "R7") (pin "2") (pinfunction "2_2") (pintype "passive"))
      (node (ref "U$3") (pin "25") (pinfunction "GPIO5/I2C_MCLK_25") (pintype "bidirectional"))
    )
    (net (code "55") (name "Net-(U$3-RCAP)") (class "Default")
      (node (ref "C12") (pin "1") (pinfunction "1_1") (pintype "passive"))
      (node (ref "U$3") (pin "44") (pinfunction "RCAP_44") (pintype "bidirectional"))
    )
    (net (code "56") (name "Net-(U$3-XTAL1{slash}MCLK)") (class "Default")
      (node (ref "C9") (pin "2") (pinfunction "2_2") (pintype "passive"))
      (node (ref "R6") (pin "2") (pinfunction "2_2") (pintype "passive"))
      (node (ref "U$3") (pin "18") (pinfunction "XTAL1/MCLK_18") (pintype "bidirectional"))
      (node (ref "Y1") (pin "3") (pinfunction "2_3") (pintype "passive"))
    )
    (net (code "57") (name "Net-(U$3-XTAL2)") (class "Default")
      (node (ref "C10") (pin "2") (pinfunction "2_2") (pintype "passive"))
      (node (ref "R6") (pin "1") (pinfunction "1_1") (pintype "passive"))
      (node (ref "U$3") (pin "17") (pinfunction "XTAL2_17") (pintype "bidirectional"))
      (node (ref "Y1") (pin "1") (pinfunction "1_1") (pintype "passive"))
    )
    (net (code "58") (name "Net-(U$4-DOWN)") (class "Default")
      (node (ref "S3") (pin "1") (pinfunction "2_1") (pintype "passive"))
      (node (ref "S3") (pin "4") (pinfunction "2_4") (pintype "passive"))
      (node (ref "U$4") (pin "5") (pinfunction "DOWN_5") (pintype "bidirectional"))
    )
    (net (code "59") (name "Net-(U$4-LINN)") (class "Default")
      (node (ref "C26") (pin "2") (pinfunction "2_2") (pintype "passive"))
      (node (ref "U$4") (pin "7") (pinfunction "LINN_7") (pintype "bidirectional"))
    )
    (net (code "60") (name "Net-(U$4-LINP)") (class "Default")
      (node (ref "C27") (pin "2") (pinfunction "2_2") (pintype "passive"))
      (node (ref "U$4") (pin "8") (pinfunction "LINP_8") (pintype "bidirectional"))
    )
    (net (code "61") (name "Net-(U$4-LOUTN)") (class "Default")
      (node (ref "L3") (pin "1") (pinfunction "1_1") (pintype "passive"))
      (node (ref "U$4") (pin "11") (pinfunction "LOUTN_11") (pintype "bidirectional"))
    )
    (net (code "62") (name "Net-(U$4-LOUTP)") (class "Default")
      (node (ref "L4") (pin "1") (pinfunction "1_1") (pintype "passive"))
      (node (ref "U$4") (pin "10") (pinfunction "LOUTP_10") (pintype "bidirectional"))
    )
    (net (code "63") (name "Net-(U$4-RINN)") (class "Default")
      (node (ref "C25") (pin "2") (pinfunction "2_2") (pintype "passive"))
      (node (ref "U$4") (pin "2") (pinfunction "RINN_2") (pintype "bidirectional"))
    )
    (net (code "64") (name "Net-(U$4-RINP)") (class "Default")
      (node (ref "C24") (pin "2") (pinfunction "2_2") (pintype "passive"))
      (node (ref "U$4") (pin "1") (pinfunction "RINP_1") (pintype "bidirectional"))
    )
    (net (code "65") (name "Net-(U$4-ROUTN)") (class "Default")
      (node (ref "L2") (pin "1") (pinfunction "1_1") (pintype "passive"))
      (node (ref "U$4") (pin "14") (pinfunction "ROUTN_14") (pintype "bidirectional"))
    )
    (net (code "66") (name "Net-(U$4-ROUTP)") (class "Default")
      (node (ref "L1") (pin "1") (pinfunction "1_1") (pintype "passive"))
      (node (ref "U$4") (pin "15") (pinfunction "ROUTP_15") (pintype "bidirectional"))
    )
    (net (code "67") (name "Net-(U$4-UP)") (class "Default")
      (node (ref "S2") (pin "1") (pinfunction "2_1") (pintype "passive"))
      (node (ref "S2") (pin "4") (pinfunction "2_4") (pintype "passive"))
      (node (ref "U$4") (pin "4") (pinfunction "UP_4") (pintype "bidirectional"))
    )
    (net (code "68") (name "Net-(U1-PB6(XTAL1{slash}TOSC1))") (class "Default")
      (node (ref "U1") (pin "7") (pinfunction "PB6(XTAL1/TOSC1)_7") (pintype "bidirectional"))
      (node (ref "Y2") (pin "1") (pinfunction "1_1") (pintype "passive"))
    )
    (net (code "69") (name "Net-(U1-PB7(XTAL2{slash}TOSC2))") (class "Default")
      (node (ref "U1") (pin "8") (pinfunction "PB7(XTAL2/TOSC2)_8") (pintype "bidirectional"))
      (node (ref "Y2") (pin "3") (pinfunction "3_3") (pintype "passive"))
    )
    (net (code "70") (name "Net-(U2-BP)") (class "Default")
      (node (ref "C2") (pin "1") (pinfunction "1_1") (pintype "passive"))
      (node (ref "U2") (pin "4") (pinfunction "BP_4") (pintype "input"))
    )
    (net (code "71") (name "Net-(U3-PROG)") (class "Default")
      (node (ref "R3") (pin "2") (pinfunction "2_2") (pintype "passive"))
      (node (ref "R4") (pin "2") (pinfunction "2_2") (pintype "passive"))
      (node (ref "U3") (pin "5") (pinfunction "PROG_5") (pintype "input"))
    )
    (net (code "72") (name "Net-(U3-STAT)") (class "Default")
      (node (ref "D4") (pin "C") (pinfunction "C_C") (pintype "passive"))
      (node (ref "U3") (pin "1") (pinfunction "STAT_1") (pintype "output"))
    )
    (net (code "73") (name "unconnected-(J4-RSV-PadRSV1)") (class "Default")
      (node (ref "J4") (pin "RSV1") (pinfunction "RSV_RSV1") (pintype "bidirectional"))
    )
    (net (code "74") (name "unconnected-(J4-RSV-PadRSV2)") (class "Default")
      (node (ref "J4") (pin "RSV2") (pinfunction "RSV_RSV2") (pintype "bidirectional"))
    )
    (net (code "75") (name "unconnected-(S1-S-Pad3)") (class "Default")
      (node (ref "S1") (pin "3") (pinfunction "S_3") (pintype "passive"))
    )
    (net (code "76") (name "unconnected-(U$1-NC-Pad4)") (class "Default")
      (node (ref "U$1") (pin "4") (pinfunction "NC_4") (pintype "no_connect"))
    )
    (net (code "77") (name "unconnected-(U$3-LINEIN-Pad48)") (class "Default")
      (node (ref "U$3") (pin "48") (pinfunction "LINEIN_48") (pintype "bidirectional"))
    )
    (net (code "78") (name "unconnected-(U$3-MICN-Pad2)") (class "Default")
      (node (ref "U$3") (pin "2") (pinfunction "MICN_2") (pintype "bidirectional"))
    )
    (net (code "79") (name "unconnected-(U$3-MICP-Pad1)") (class "Default")
      (node (ref "U$3") (pin "1") (pinfunction "MICP_1") (pintype "bidirectional"))
    )
    (net (code "80") (name "unconnected-(U$3-TX-Pad27)") (class "Default")
      (node (ref "U$3") (pin "27") (pinfunction "TX_27") (pintype "bidirectional"))
    )
    (net (code "81") (name "unconnected-(U$3-VCO-Pad15)") (class "Default")
      (node (ref "U$3") (pin "15") (pinfunction "VCO_15") (pintype "bidirectional"))
    )
  )
)
